# KlokWave.net
KiCad netlist of a schematic drawn in Altium Designer
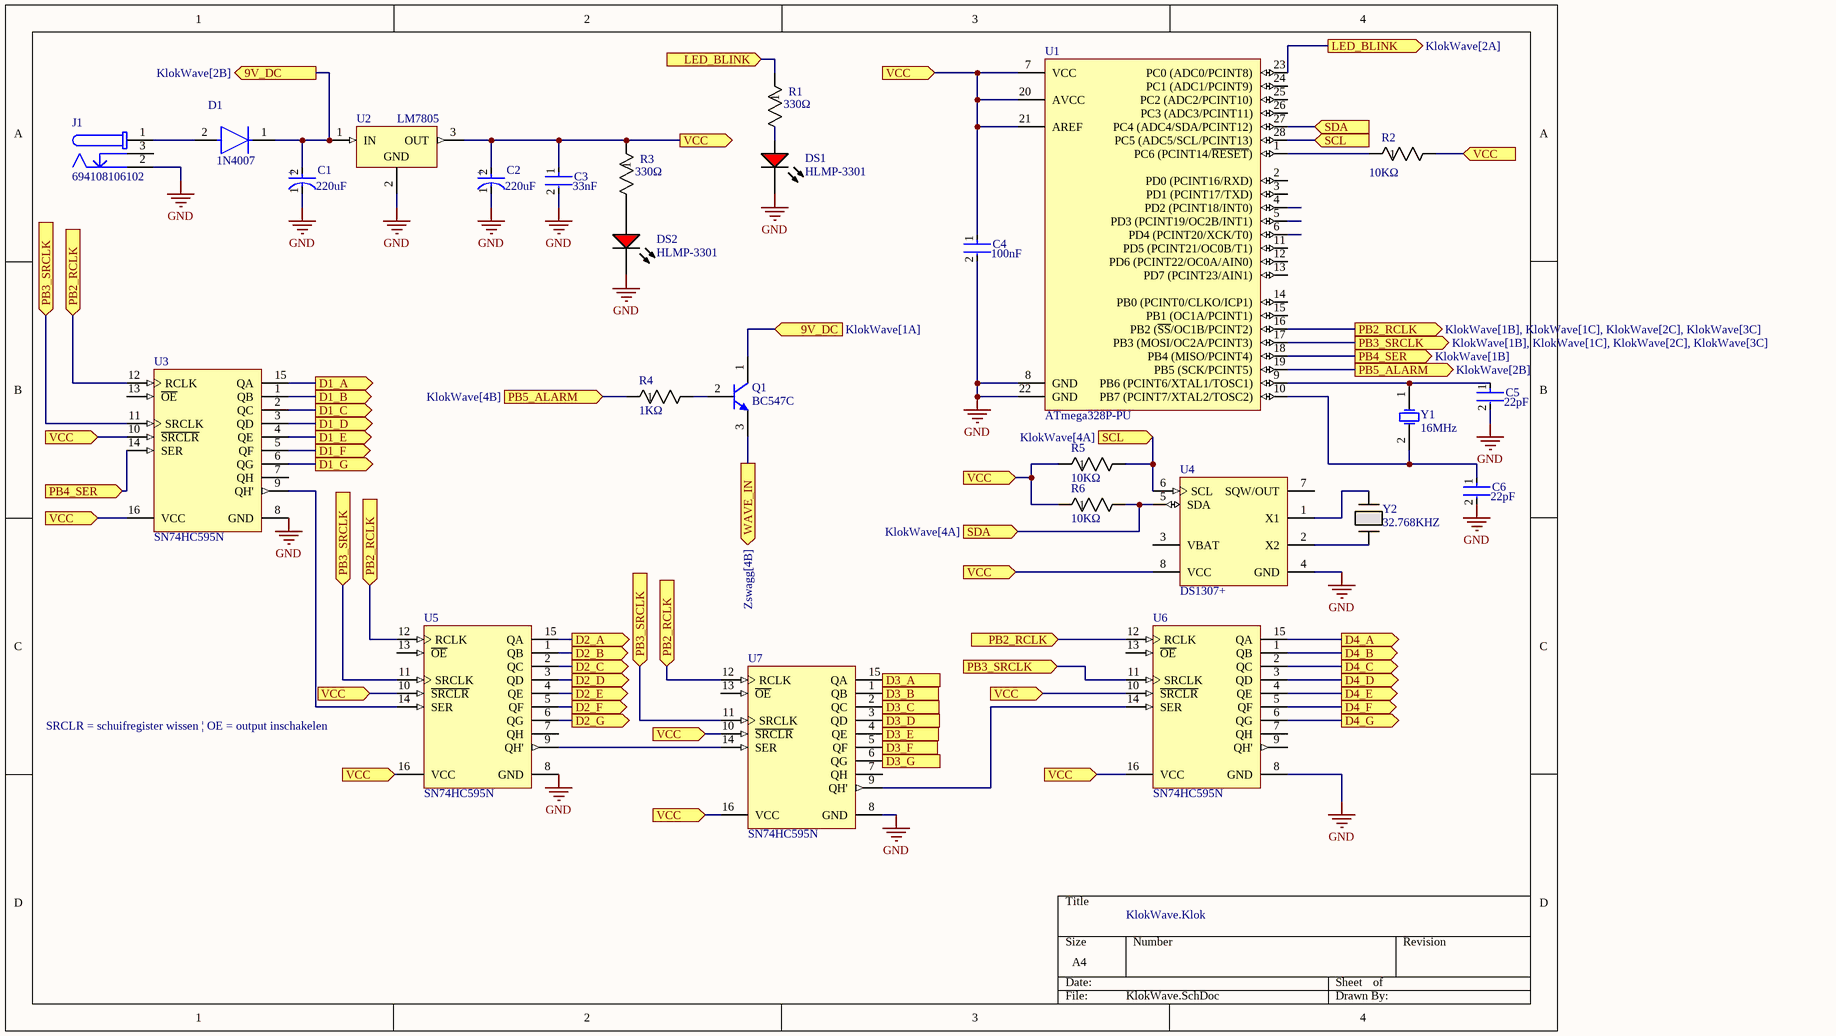
[diagram p0: KlokWave.SchDoc]

(export (version "E")
  (design (tool "Eeschema 10.0.6"))
  (components
    (comp (ref "C1")
      (value "16SEPC150MD")
      (footprint "FP-OS-CON-TH-E7-d_0_45-MFG")
      (description "Conductive Polymer Aluminum Solid Capacitors (OS-CON) 150uF ±20% 16V RADIAL TH 8x7mm")
      (fields
        (field (name "VOLTAGE") "16V")
        (field (name "TOLERANCE") "20%")
        (field (name "CAPACITANCE") "220uF")
      )
      (libsource (lib "KlokWave") (part "CMP-05428-000489-1"))
    )
    (comp (ref "C2")
      (value "16SEPC150MD")
      (footprint "FP-OS-CON-TH-E7-d_0_45-MFG")
      (description "Conductive Polymer Aluminum Solid Capacitors (OS-CON) 150uF ±20% 16V RADIAL TH 8x7mm")
      (fields
        (field (name "VOLTAGE") "16V")
        (field (name "TOLERANCE") "20%")
        (field (name "CAPACITANCE") "220uF")
      )
      (libsource (lib "KlokWave") (part "CMP-05428-000489-1"))
    )
    (comp (ref "C3")
      (value "565R30GASS33")
      (footprint "FP-565R30GASS33-MFG")
      (description "565R30GASS33 33nF 3 kV dc THT Ceramic Single Layer Capacitor; Z5U Dielectric Radial 565R Series")
      (fields
        (field (name "VOLTAGE") "3kV")
        (field (name "TOLERANCE") "20%")
        (field (name "CAPACITANCE") "33nF")
      )
      (libsource (lib "KlokWave") (part "CMP-00030-41968055-1"))
    )
    (comp (ref "C4")
      (value "565R30GASS33")
      (footprint "FP-565R30GASS33-MFG")
      (description "565R30GASS33 33nF 3 kV dc THT Ceramic Single Layer Capacitor; Z5U Dielectric Radial 565R Series")
      (fields
        (field (name "VOLTAGE") "3kV")
        (field (name "TOLERANCE") "20%")
        (field (name "CAPACITANCE") "100nF")
      )
      (libsource (lib "KlokWave") (part "CMP-00030-41968055-1"))
    )
    (comp (ref "C5")
      (value "565R30GASS33")
      (footprint "FP-565R30GASS33-MFG")
      (description "565R30GASS33 33nF 3 kV dc THT Ceramic Single Layer Capacitor; Z5U Dielectric Radial 565R Series")
      (fields
        (field (name "VOLTAGE") "3kV")
        (field (name "TOLERANCE") "20%")
        (field (name "CAPACITANCE") "22pF")
      )
      (libsource (lib "KlokWave") (part "CMP-00030-41968055-1"))
    )
    (comp (ref "C6")
      (value "565R30GASS33")
      (footprint "FP-565R30GASS33-MFG")
      (description "565R30GASS33 33nF 3 kV dc THT Ceramic Single Layer Capacitor; Z5U Dielectric Radial 565R Series")
      (fields
        (field (name "VOLTAGE") "3kV")
        (field (name "TOLERANCE") "20%")
        (field (name "CAPACITANCE") "22pF")
      )
      (libsource (lib "KlokWave") (part "CMP-00030-41968055-1"))
    )
    (comp (ref "D1")
      (value "1N4007")
      (footprint "FP-1N4007-E3-53-MFG")
      (description "1N4007 DIODE GEN PURP 1KV 1A DO204AL")
      (libsource (lib "KlokWave") (part "CMP-02540-000066-1"))
    )
    (comp (ref "DS1")
      (value "HLMP-3301")
      (footprint "AVAG-HLMP-3301-2")
      (description "T-1 3/4 (5 mm) Diffused LED Lamp, 1.9 V, -40 to 100 degC, 2-Pin THD")
      (fields (field (name "MANUFACTURER") "Avago"))
      (libsource (lib "KlokWave") (part "CMP-2000-06411-1"))
    )
    (comp (ref "DS2")
      (value "HLMP-3301")
      (footprint "AVAG-HLMP-3301-2")
      (description "T-1 3/4 (5 mm) Diffused LED Lamp, 1.9 V, -40 to 100 degC, 2-Pin THD")
      (fields (field (name "MANUFACTURER") "Avago"))
      (libsource (lib "KlokWave") (part "CMP-2000-06411-1"))
    )
    (comp (ref "J1")
      (value "694108106102")
      (footprint "694108106102")
      (description "DC Power JAck")
      (libsource (lib "KlokWave") (part "CMP-1502-00180-2"))
    )
    (comp (ref "Q1")
      (value "BC547C")
      (footprint "ONSC-TO-92-3-29-11")
      (description "BC547C: THT Amplifier Transistor, NPN Silicon, 3-Pin TO-92, Bulk Box")
      (fields (field (name "MANUFACTURER") "On Semiconductor"))
      (libsource (lib "KlokWave") (part "CMP-1048-01437-1"))
    )
    (comp (ref "R1")
      (value "AC03000003000JAC00")
      (footprint "RES_AC03_VIS")
      (description "AC03000003000JAC00 Res Wirewound THT")
      (fields (field (name "TOLERANCE") "5%") (field (name "RESISTANCE") "330Ω"))
      (libsource (lib "KlokWave") (part "CMP-00030-39746760-1"))
    )
    (comp (ref "R2")
      (value "AC03000003000JAC00")
      (footprint "RES_AC03_VIS")
      (description "AC03000003000JAC00 Res Wirewound THT")
      (fields (field (name "TOLERANCE") "5%") (field (name "RESISTANCE") "10KΩ"))
      (libsource (lib "KlokWave") (part "CMP-00030-39746760-1"))
    )
    (comp (ref "R3")
      (value "AC03000003000JAC00")
      (footprint "RES_AC03_VIS")
      (description "AC03000003000JAC00 Res Wirewound THT")
      (fields (field (name "TOLERANCE") "5%") (field (name "RESISTANCE") "330Ω"))
      (libsource (lib "KlokWave") (part "CMP-00030-39746760-1"))
    )
    (comp (ref "R4")
      (value "AC03000003000JAC00")
      (footprint "RES_AC03_VIS")
      (description "AC03000003000JAC00 Res Wirewound THT")
      (fields (field (name "TOLERANCE") "5%") (field (name "RESISTANCE") "1KΩ"))
      (libsource (lib "KlokWave") (part "CMP-00030-39746760-1"))
    )
    (comp (ref "R5")
      (value "AC03000003000JAC00")
      (footprint "RES_AC03_VIS")
      (description "AC03000003000JAC00 Res Wirewound THT")
      (fields (field (name "TOLERANCE") "5%") (field (name "RESISTANCE") "10KΩ"))
      (libsource (lib "KlokWave") (part "CMP-00030-39746760-1"))
    )
    (comp (ref "R6")
      (value "AC03000003000JAC00")
      (footprint "RES_AC03_VIS")
      (description "AC03000003000JAC00 Res Wirewound THT")
      (fields (field (name "TOLERANCE") "5%") (field (name "RESISTANCE") "10KΩ"))
      (libsource (lib "KlokWave") (part "CMP-00030-39746760-1"))
    )
    (comp (ref "U1")
      (value "ATmega328P-PU")
      (footprint "28P3")
      (libsource (lib "KlokWave") (part "CMP-0095-00013-2"))
    )
    (comp (ref "U2")
      (value "LM7805")
      (footprint "FAIR-TO-220-3")
      (description "Positive Voltage Regulator, 5 V, 1 A, 0 to 125 degC, 3-Pin TO-220, RoHS, Tube")
      (fields (field (name "MANUFACTURER") "Fairchild"))
      (libsource (lib "KlokWave") (part "CMP-2000-04937-1"))
    )
    (comp (ref "U3")
      (value "SN74HC595N")
      (footprint "N0016A")
      (description "8-Bit Shift Registers With 3-State Output Registers, N0016A, TUBE")
      (fields
        (field (name "GENERIC PART NUMBER") "SN74HC595")
        (field (name "MANUFACTURER") "Texas Instruments")
      )
      (libsource (lib "KlokWave") (part "CMP-0780-00137-3"))
    )
    (comp (ref "U4")
      (value "DS1307+")
      (footprint "P8+2")
      (description "64 x 8, Serial, I2C Real-Time Clock, 5.0V, 8-Pin PDIP, 0 to 70 degC, Pb-Free")
      (libsource (lib "KlokWave") (part "CMP-0254-00152-1"))
    )
    (comp (ref "U5")
      (value "SN74HC595N")
      (footprint "N0016A")
      (description "8-Bit Shift Registers With 3-State Output Registers, N0016A, TUBE")
      (fields
        (field (name "GENERIC PART NUMBER") "SN74HC595")
        (field (name "MANUFACTURER") "Texas Instruments")
      )
      (libsource (lib "KlokWave") (part "CMP-0780-00137-3"))
    )
    (comp (ref "U6")
      (value "SN74HC595N")
      (footprint "N0016A")
      (description "8-Bit Shift Registers With 3-State Output Registers, N0016A, TUBE")
      (fields
        (field (name "GENERIC PART NUMBER") "SN74HC595")
        (field (name "MANUFACTURER") "Texas Instruments")
      )
      (libsource (lib "KlokWave") (part "CMP-0780-00137-3"))
    )
    (comp (ref "U7")
      (value "SN74HC595N")
      (footprint "N0016A")
      (description "8-Bit Shift Registers With 3-State Output Registers, N0016A, TUBE")
      (fields
        (field (name "GENERIC PART NUMBER") "SN74HC595")
        (field (name "MANUFACTURER") "Texas Instruments")
      )
      (libsource (lib "KlokWave") (part "CMP-0780-00137-3"))
    )
    (comp (ref "Y1")
      (value "16MHz")
      (footprint "WE-XTAL_HC49/4H")
      (description "THT Quartz Crystal, HC49/4H, 16MHz, +/-30ppm WE-XTAL")
      (fields
        (field (name "MANUFACTURER PART NUMBER") "830003240B")
        (field (name "MANUFACTURER") "Wurth Elektronik")
      )
      (libsource (lib "KlokWave") (part "830003240B"))
    )
    (comp (ref "Y2")
      (value "32.768KHZ")
      (footprint "XTAL_AB38T_ABR")
      (description "THT CRYSTAL 32.7680KHZ")
      (libsource (lib "KlokWave") (part "AB38T-32.768KHZ"))
    )
  )
  (nets
    (net (code "1") (name "/9V_DC") (class "Default")
      (node (ref "C1") (pin "2") (pinfunction "A_2") (pintype "passive"))
      (node (ref "D1") (pin "1") (pinfunction "C_1") (pintype "passive"))
      (node (ref "Q1") (pin "1") (pinfunction "C_1") (pintype "passive"))
      (node (ref "U2") (pin "1") (pinfunction "IN_1") (pintype "input"))
    )
    (net (code "2") (name "/D1_A") (class "Default")
      (node (ref "U3") (pin "15") (pinfunction "QA_15") (pintype "tri_state"))
    )
    (net (code "3") (name "/D1_B") (class "Default")
      (node (ref "U3") (pin "1") (pinfunction "QB_1") (pintype "tri_state"))
    )
    (net (code "4") (name "/D1_C") (class "Default")
      (node (ref "U3") (pin "2") (pinfunction "QC_2") (pintype "tri_state"))
    )
    (net (code "5") (name "/D1_D") (class "Default")
      (node (ref "U3") (pin "3") (pinfunction "QD_3") (pintype "tri_state"))
    )
    (net (code "6") (name "/D1_E") (class "Default")
      (node (ref "U3") (pin "4") (pinfunction "QE_4") (pintype "tri_state"))
    )
    (net (code "7") (name "/D1_F") (class "Default")
      (node (ref "U3") (pin "5") (pinfunction "QF_5") (pintype "tri_state"))
    )
    (net (code "8") (name "/D1_G") (class "Default")
      (node (ref "U3") (pin "6") (pinfunction "QG_6") (pintype "tri_state"))
    )
    (net (code "9") (name "/D2_A") (class "Default")
      (node (ref "U5") (pin "15") (pinfunction "QA_15") (pintype "tri_state"))
    )
    (net (code "10") (name "/D2_B") (class "Default")
      (node (ref "U5") (pin "1") (pinfunction "QB_1") (pintype "tri_state"))
    )
    (net (code "11") (name "/D2_C") (class "Default")
      (node (ref "U5") (pin "2") (pinfunction "QC_2") (pintype "tri_state"))
    )
    (net (code "12") (name "/D2_D") (class "Default")
      (node (ref "U5") (pin "3") (pinfunction "QD_3") (pintype "tri_state"))
    )
    (net (code "13") (name "/D2_E") (class "Default")
      (node (ref "U5") (pin "4") (pinfunction "QE_4") (pintype "tri_state"))
    )
    (net (code "14") (name "/D2_F") (class "Default")
      (node (ref "U5") (pin "5") (pinfunction "QF_5") (pintype "tri_state"))
    )
    (net (code "15") (name "/D2_G") (class "Default")
      (node (ref "U5") (pin "6") (pinfunction "QG_6") (pintype "tri_state"))
    )
    (net (code "16") (name "/D3_A") (class "Default")
      (node (ref "U7") (pin "15") (pinfunction "QA_15") (pintype "tri_state"))
    )
    (net (code "17") (name "/D3_B") (class "Default")
      (node (ref "U7") (pin "1") (pinfunction "QB_1") (pintype "tri_state"))
    )
    (net (code "18") (name "/D3_C") (class "Default")
      (node (ref "U7") (pin "2") (pinfunction "QC_2") (pintype "tri_state"))
    )
    (net (code "19") (name "/D3_D") (class "Default")
      (node (ref "U7") (pin "3") (pinfunction "QD_3") (pintype "tri_state"))
    )
    (net (code "20") (name "/D3_E") (class "Default")
      (node (ref "U7") (pin "4") (pinfunction "QE_4") (pintype "tri_state"))
    )
    (net (code "21") (name "/D3_F") (class "Default")
      (node (ref "U7") (pin "5") (pinfunction "QF_5") (pintype "tri_state"))
    )
    (net (code "22") (name "/D3_G") (class "Default")
      (node (ref "U7") (pin "6") (pinfunction "QG_6") (pintype "tri_state"))
    )
    (net (code "23") (name "/D4_A") (class "Default")
      (node (ref "U6") (pin "15") (pinfunction "QA_15") (pintype "tri_state"))
    )
    (net (code "24") (name "/D4_B") (class "Default")
      (node (ref "U6") (pin "1") (pinfunction "QB_1") (pintype "tri_state"))
    )
    (net (code "25") (name "/D4_C") (class "Default")
      (node (ref "U6") (pin "2") (pinfunction "QC_2") (pintype "tri_state"))
    )
    (net (code "26") (name "/D4_D") (class "Default")
      (node (ref "U6") (pin "3") (pinfunction "QD_3") (pintype "tri_state"))
    )
    (net (code "27") (name "/D4_E") (class "Default")
      (node (ref "U6") (pin "4") (pinfunction "QE_4") (pintype "tri_state"))
    )
    (net (code "28") (name "/D4_F") (class "Default")
      (node (ref "U6") (pin "5") (pinfunction "QF_5") (pintype "tri_state"))
    )
    (net (code "29") (name "/D4_G") (class "Default")
      (node (ref "U6") (pin "6") (pinfunction "QG_6") (pintype "tri_state"))
    )
    (net (code "30") (name "/LED_BLINK") (class "Default")
      (node (ref "R1") (pin "1") (pinfunction "1_1") (pintype "passive"))
      (node (ref "U1") (pin "23") (pinfunction "PC0_(ADC0/PCINT8)_23") (pintype "bidirectional"))
    )
    (net (code "31") (name "/PB2_RCLK") (class "Default")
      (node (ref "U1") (pin "16") (pinfunction "PB2_(~{SS}/OC1B/PCINT2)_16") (pintype "bidirectional"))
      (node (ref "U3") (pin "12") (pinfunction "RCLK_12") (pintype "input"))
      (node (ref "U5") (pin "12") (pinfunction "RCLK_12") (pintype "input"))
      (node (ref "U6") (pin "12") (pinfunction "RCLK_12") (pintype "input"))
      (node (ref "U7") (pin "12") (pinfunction "RCLK_12") (pintype "input"))
    )
    (net (code "32") (name "/PB3_SRCLK") (class "Default")
      (node (ref "U1") (pin "17") (pinfunction "PB3_(MOSI/OC2A/PCINT3)_17") (pintype "bidirectional"))
      (node (ref "U3") (pin "11") (pinfunction "SRCLK_11") (pintype "input"))
      (node (ref "U5") (pin "11") (pinfunction "SRCLK_11") (pintype "input"))
      (node (ref "U6") (pin "11") (pinfunction "SRCLK_11") (pintype "input"))
      (node (ref "U7") (pin "11") (pinfunction "SRCLK_11") (pintype "input"))
    )
    (net (code "33") (name "/PB4_SER") (class "Default")
      (node (ref "U1") (pin "18") (pinfunction "PB4_(MISO/PCINT4)_18") (pintype "bidirectional"))
      (node (ref "U3") (pin "14") (pinfunction "SER_14") (pintype "input"))
    )
    (net (code "34") (name "/PB5_ALARM") (class "Default")
      (node (ref "R4") (pin "1") (pinfunction "1_1") (pintype "passive"))
      (node (ref "U1") (pin "19") (pinfunction "PB5_(SCK/PCINT5)_19") (pintype "bidirectional"))
    )
    (net (code "35") (name "/SCL") (class "Default")
      (node (ref "R5") (pin "2") (pinfunction "2_2") (pintype "passive"))
      (node (ref "U1") (pin "28") (pinfunction "PC5_(ADC5/SCL/PCINT13)_28") (pintype "bidirectional"))
      (node (ref "U4") (pin "6") (pinfunction "SCL_6") (pintype "input"))
    )
    (net (code "36") (name "/SDA") (class "Default")
      (node (ref "R6") (pin "2") (pinfunction "2_2") (pintype "passive"))
      (node (ref "U1") (pin "27") (pinfunction "PC4_(ADC4/SDA/PCINT12)_27") (pintype "bidirectional"))
      (node (ref "U4") (pin "5") (pinfunction "SDA_5") (pintype "bidirectional"))
    )
    (net (code "37") (name "/VCC") (class "Default")
      (node (ref "C2") (pin "2") (pinfunction "A_2") (pintype "passive"))
      (node (ref "C3") (pin "1") (pinfunction "1_1") (pintype "passive"))
      (node (ref "C4") (pin "1") (pinfunction "1_1") (pintype "passive"))
      (node (ref "R2") (pin "2") (pinfunction "2_2") (pintype "passive"))
      (node (ref "R3") (pin "1") (pinfunction "1_1") (pintype "passive"))
      (node (ref "R5") (pin "1") (pinfunction "1_1") (pintype "passive"))
      (node (ref "R6") (pin "1") (pinfunction "1_1") (pintype "passive"))
      (node (ref "U1") (pin "20") (pinfunction "AVCC_20") (pintype "power_in"))
      (node (ref "U1") (pin "21") (pinfunction "AREF_21") (pintype "power_in"))
      (node (ref "U1") (pin "7") (pinfunction "VCC_7") (pintype "power_in"))
      (node (ref "U2") (pin "3") (pinfunction "OUT_3") (pintype "output"))
      (node (ref "U3") (pin "10") (pinfunction "~{SRCLR}_10") (pintype "input"))
      (node (ref "U3") (pin "16") (pinfunction "VCC_16") (pintype "power_in"))
      (node (ref "U4") (pin "8") (pinfunction "VCC_8") (pintype "power_in"))
      (node (ref "U5") (pin "10") (pinfunction "~{SRCLR}_10") (pintype "input"))
      (node (ref "U5") (pin "16") (pinfunction "VCC_16") (pintype "power_in"))
      (node (ref "U6") (pin "10") (pinfunction "~{SRCLR}_10") (pintype "input"))
      (node (ref "U6") (pin "16") (pinfunction "VCC_16") (pintype "power_in"))
      (node (ref "U7") (pin "10") (pinfunction "~{SRCLR}_10") (pintype "input"))
      (node (ref "U7") (pin "16") (pinfunction "VCC_16") (pintype "power_in"))
    )
    (net (code "38") (name "/WAVE_IN") (class "Default")
      (node (ref "Q1") (pin "3") (pinfunction "E_3") (pintype "passive"))
    )
    (net (code "39") (name "GND") (class "Default")
      (node (ref "C1") (pin "1") (pinfunction "C_1") (pintype "passive"))
      (node (ref "C2") (pin "1") (pinfunction "C_1") (pintype "passive"))
      (node (ref "C3") (pin "2") (pinfunction "2_2") (pintype "passive"))
      (node (ref "C4") (pin "2") (pinfunction "2_2") (pintype "passive"))
      (node (ref "C5") (pin "2") (pinfunction "2_2") (pintype "passive"))
      (node (ref "C6") (pin "2") (pinfunction "2_2") (pintype "passive"))
      (node (ref "DS1") (pin "1") (pinfunction "K_1") (pintype "passive"))
      (node (ref "DS2") (pin "1") (pinfunction "K_1") (pintype "passive"))
      (node (ref "J1") (pin "2") (pinfunction "2_2") (pintype "passive"))
      (node (ref "U1") (pin "22") (pinfunction "GND_22") (pintype "power_in"))
      (node (ref "U1") (pin "8") (pinfunction "GND_8") (pintype "power_in"))
      (node (ref "U2") (pin "2") (pinfunction "GND_2") (pintype "power_in"))
      (node (ref "U3") (pin "8") (pinfunction "GND_8") (pintype "power_in"))
      (node (ref "U4") (pin "4") (pinfunction "GND_4") (pintype "power_in"))
      (node (ref "U5") (pin "8") (pinfunction "GND_8") (pintype "power_in"))
      (node (ref "U6") (pin "8") (pinfunction "GND_8") (pintype "power_in"))
      (node (ref "U7") (pin "8") (pinfunction "GND_8") (pintype "power_in"))
    )
    (net (code "40") (name "Net-(D1-A)") (class "Default")
      (node (ref "D1") (pin "2") (pinfunction "A_2") (pintype "passive"))
      (node (ref "J1") (pin "1") (pinfunction "1_1") (pintype "passive"))
    )
    (net (code "41") (name "Net-(DS1-A)") (class "Default")
      (node (ref "DS1") (pin "2") (pinfunction "A_2") (pintype "passive"))
      (node (ref "R1") (pin "2") (pinfunction "2_2") (pintype "passive"))
    )
    (net (code "42") (name "Net-(DS2-A)") (class "Default")
      (node (ref "DS2") (pin "2") (pinfunction "A_2") (pintype "passive"))
      (node (ref "R3") (pin "2") (pinfunction "2_2") (pintype "passive"))
    )
    (net (code "43") (name "Net-(Q1-B)") (class "Default")
      (node (ref "Q1") (pin "2") (pinfunction "B_2") (pintype "passive"))
      (node (ref "R4") (pin "2") (pinfunction "2_2") (pintype "passive"))
    )
    (net (code "44") (name "Net-(U1-PB6_(PCINT6{slash}XTAL1{slash}TOSC1))") (class "Default")
      (node (ref "C5") (pin "1") (pinfunction "1_1") (pintype "passive"))
      (node (ref "U1") (pin "9") (pinfunction "PB6_(PCINT6/XTAL1/TOSC1)_9") (pintype "bidirectional"))
      (node (ref "Y1") (pin "1") (pinfunction "OSC1_1") (pintype "passive"))
    )
    (net (code "45") (name "Net-(U1-PB7_(PCINT7{slash}XTAL2{slash}TOSC2))") (class "Default")
      (node (ref "C6") (pin "1") (pinfunction "1_1") (pintype "passive"))
      (node (ref "U1") (pin "10") (pinfunction "PB7_(PCINT7/XTAL2/TOSC2)_10") (pintype "bidirectional"))
      (node (ref "Y1") (pin "2") (pinfunction "OSC2_2") (pintype "passive"))
    )
    (net (code "46") (name "Net-(U1-PC6_(PCINT14{slash}~{RESET}))") (class "Default")
      (node (ref "R2") (pin "1") (pinfunction "1_1") (pintype "passive"))
      (node (ref "U1") (pin "1") (pinfunction "PC6_(PCINT14/~{RESET})_1") (pintype "bidirectional"))
    )
    (net (code "47") (name "Net-(U3-QH')") (class "Default")
      (node (ref "U3") (pin "9") (pinfunction "QH'_9") (pintype "output"))
      (node (ref "U5") (pin "14") (pinfunction "SER_14") (pintype "input"))
    )
    (net (code "48") (name "Net-(U4-X1)") (class "Default")
      (node (ref "U4") (pin "1") (pinfunction "X1_1") (pintype "passive"))
      (node (ref "Y2") (pin "1") (pinfunction "1_1") (pintype "passive"))
    )
    (net (code "49") (name "Net-(U4-X2)") (class "Default")
      (node (ref "U4") (pin "2") (pinfunction "X2_2") (pintype "passive"))
      (node (ref "Y2") (pin "2") (pinfunction "2_2") (pintype "passive"))
    )
    (net (code "50") (name "Net-(U5-QH')") (class "Default")
      (node (ref "U5") (pin "9") (pinfunction "QH'_9") (pintype "output"))
      (node (ref "U7") (pin "14") (pinfunction "SER_14") (pintype "input"))
    )
    (net (code "51") (name "Net-(U6-SER)") (class "Default")
      (node (ref "U6") (pin "14") (pinfunction "SER_14") (pintype "input"))
      (node (ref "U7") (pin "9") (pinfunction "QH'_9") (pintype "output"))
    )
    (net (code "52") (name "unconnected-(J1-Pad3)") (class "Default")
      (node (ref "J1") (pin "3") (pinfunction "3_3") (pintype "passive"))
    )
    (net (code "53") (name "unconnected-(U1-PB0_(PCINT0{slash}CLKO{slash}ICP1)-Pad14)") (class "Default")
      (node (ref "U1") (pin "14") (pinfunction "PB0_(PCINT0/CLKO/ICP1)_14") (pintype "bidirectional"))
    )
    (net (code "54") (name "unconnected-(U1-PB1_(OC1A{slash}PCINT1)-Pad15)") (class "Default")
      (node (ref "U1") (pin "15") (pinfunction "PB1_(OC1A/PCINT1)_15") (pintype "bidirectional"))
    )
    (net (code "55") (name "unconnected-(U1-PC1_(ADC1{slash}PCINT9)-Pad24)") (class "Default")
      (node (ref "U1") (pin "24") (pinfunction "PC1_(ADC1/PCINT9)_24") (pintype "bidirectional"))
    )
    (net (code "56") (name "unconnected-(U1-PC2_(ADC2{slash}PCINT10)-Pad25)") (class "Default")
      (node (ref "U1") (pin "25") (pinfunction "PC2_(ADC2/PCINT10)_25") (pintype "bidirectional"))
    )
    (net (code "57") (name "unconnected-(U1-PC3_(ADC3{slash}PCINT11)-Pad26)") (class "Default")
      (node (ref "U1") (pin "26") (pinfunction "PC3_(ADC3/PCINT11)_26") (pintype "bidirectional"))
    )
    (net (code "58") (name "unconnected-(U1-PD0_(PCINT16{slash}RXD)-Pad2)") (class "Default")
      (node (ref "U1") (pin "2") (pinfunction "PD0_(PCINT16/RXD)_2") (pintype "bidirectional"))
    )
    (net (code "59") (name "unconnected-(U1-PD1_(PCINT17{slash}TXD)-Pad3)") (class "Default")
      (node (ref "U1") (pin "3") (pinfunction "PD1_(PCINT17/TXD)_3") (pintype "bidirectional"))
    )
    (net (code "60") (name "unconnected-(U1-PD2_(PCINT18{slash}INT0)-Pad4)") (class "Default")
      (node (ref "U1") (pin "4") (pinfunction "PD2_(PCINT18/INT0)_4") (pintype "bidirectional"))
    )
    (net (code "61") (name "unconnected-(U1-PD3_(PCINT19{slash}OC2B{slash}INT1)-Pad5)") (class "Default")
      (node (ref "U1") (pin "5") (pinfunction "PD3_(PCINT19/OC2B/INT1)_5") (pintype "bidirectional"))
    )
    (net (code "62") (name "unconnected-(U1-PD4_(PCINT20{slash}XCK{slash}T0)-Pad6)") (class "Default")
      (node (ref "U1") (pin "6") (pinfunction "PD4_(PCINT20/XCK/T0)_6") (pintype "bidirectional"))
    )
    (net (code "63") (name "unconnected-(U1-PD5_(PCINT21{slash}OC0B{slash}T1)-Pad11)") (class "Default")
      (node (ref "U1") (pin "11") (pinfunction "PD5_(PCINT21/OC0B/T1)_11") (pintype "bidirectional"))
    )
    (net (code "64") (name "unconnected-(U1-PD6_(PCINT22{slash}OC0A{slash}AIN0)-Pad12)") (class "Default")
      (node (ref "U1") (pin "12") (pinfunction "PD6_(PCINT22/OC0A/AIN0)_12") (pintype "bidirectional"))
    )
    (net (code "65") (name "unconnected-(U1-PD7_(PCINT23{slash}AIN1)-Pad13)") (class "Default")
      (node (ref "U1") (pin "13") (pinfunction "PD7_(PCINT23/AIN1)_13") (pintype "bidirectional"))
    )
    (net (code "66") (name "unconnected-(U3-QH-Pad7)") (class "Default")
      (node (ref "U3") (pin "7") (pinfunction "QH_7") (pintype "tri_state"))
    )
    (net (code "67") (name "unconnected-(U3-~{OE}-Pad13)") (class "Default")
      (node (ref "U3") (pin "13") (pinfunction "~{OE}_13") (pintype "input"))
    )
    (net (code "68") (name "unconnected-(U4-SQW{slash}OUT-Pad7)") (class "Default")
      (node (ref "U4") (pin "7") (pinfunction "SQW/OUT_7") (pintype "open_collector"))
    )
    (net (code "69") (name "unconnected-(U4-VBAT-Pad3)") (class "Default")
      (node (ref "U4") (pin "3") (pinfunction "VBAT_3") (pintype "power_in"))
    )
    (net (code "70") (name "unconnected-(U5-QH-Pad7)") (class "Default")
      (node (ref "U5") (pin "7") (pinfunction "QH_7") (pintype "tri_state"))
    )
    (net (code "71") (name "unconnected-(U5-~{OE}-Pad13)") (class "Default")
      (node (ref "U5") (pin "13") (pinfunction "~{OE}_13") (pintype "input"))
    )
    (net (code "72") (name "unconnected-(U6-QH'-Pad9)") (class "Default")
      (node (ref "U6") (pin "9") (pinfunction "QH'_9") (pintype "output"))
    )
    (net (code "73") (name "unconnected-(U6-QH-Pad7)") (class "Default")
      (node (ref "U6") (pin "7") (pinfunction "QH_7") (pintype "tri_state"))
    )
    (net (code "74") (name "unconnected-(U6-~{OE}-Pad13)") (class "Default")
      (node (ref "U6") (pin "13") (pinfunction "~{OE}_13") (pintype "input"))
    )
    (net (code "75") (name "unconnected-(U7-QH-Pad7)") (class "Default")
      (node (ref "U7") (pin "7") (pinfunction "QH_7") (pintype "tri_state"))
    )
    (net (code "76") (name "unconnected-(U7-~{OE}-Pad13)") (class "Default")
      (node (ref "U7") (pin "13") (pinfunction "~{OE}_13") (pintype "input"))
    )
  )
)
